# SparkFun-LSM9DS1-Breakout.net
KiCad netlist of a schematic drawn in EAGLE
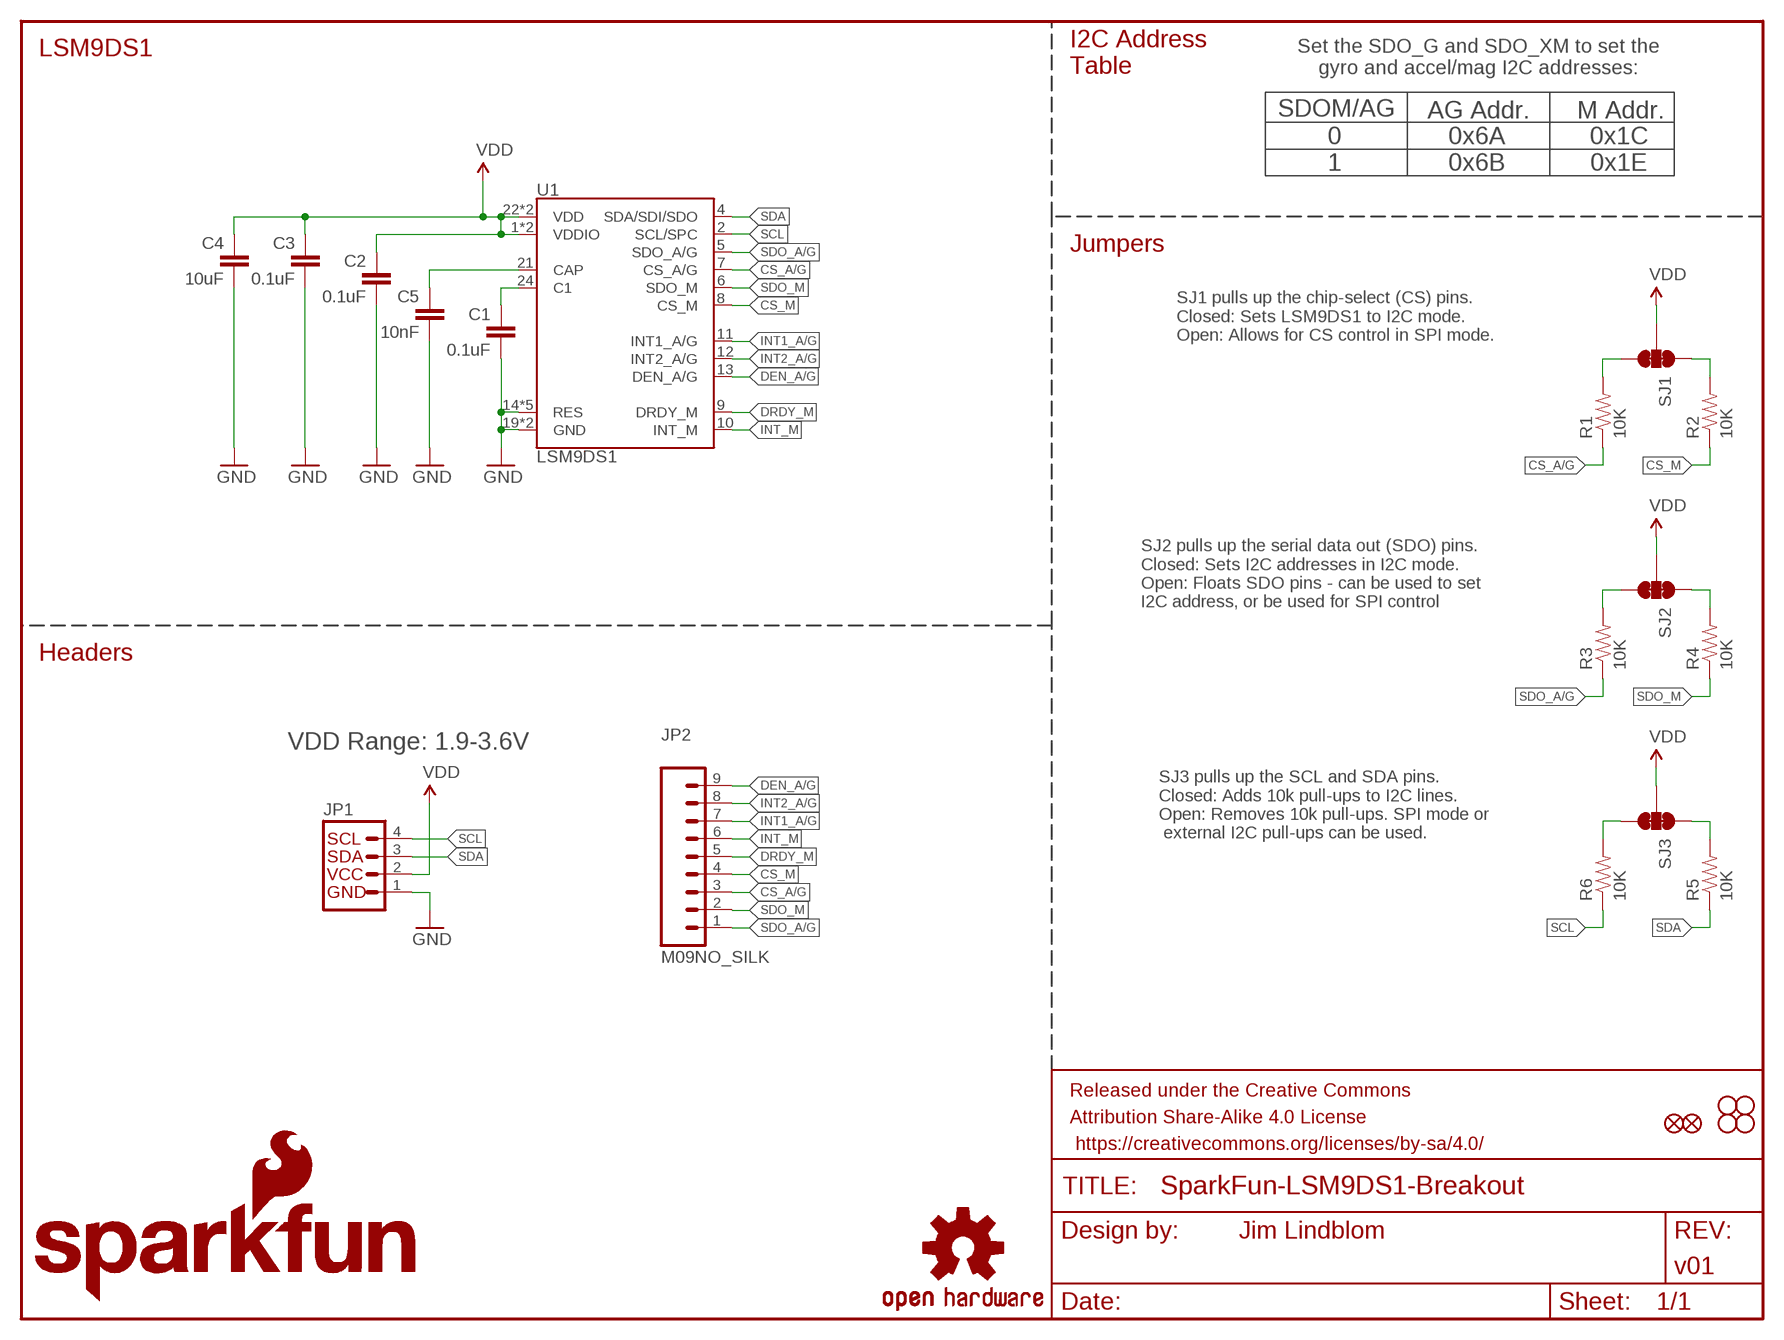
[diagram p0: schematic, sheet 1]

(export (version "E")
  (design (tool "Eeschema 10.0.6"))
  (components
    (comp (ref "C1")
      (value "0.1uF")
      (footprint "eagle-import:0603-CAP")
      (libsource (lib "eagle-import") (part "0.1UF-25V(+80/-20%)(0603)"))
    )
    (comp (ref "C2")
      (value "0.1uF")
      (footprint "eagle-import:0603-CAP")
      (libsource (lib "eagle-import") (part "0.1UF-25V(+80/-20%)(0603)"))
    )
    (comp (ref "C3")
      (value "0.1uF")
      (footprint "eagle-import:0603-CAP")
      (libsource (lib "eagle-import") (part "0.1UF-25V(+80/-20%)(0603)"))
    )
    (comp (ref "C4")
      (value "10uF")
      (footprint "eagle-import:0603-CAP")
      (libsource (lib "eagle-import") (part "10UF-6.3V-20%(0603)"))
    )
    (comp (ref "C5")
      (value "10nF")
      (footprint "eagle-import:0603-CAP")
      (libsource (lib "eagle-import") (part "10NF/10000PF-50V-10%(0603)"))
    )
    (comp (ref "FID1")
      (value "FIDUCIAL1X2")
      (footprint "eagle-import:FIDUCIAL-1X2")
      (libsource (lib "eagle-import") (part "FIDUCIAL1X2"))
    )
    (comp (ref "FID2")
      (value "FIDUCIAL1X2")
      (footprint "eagle-import:FIDUCIAL-1X2")
      (libsource (lib "eagle-import") (part "FIDUCIAL1X2"))
    )
    (comp (ref "FRAME1")
      (value "FRAME-LETTER")
      (footprint "eagle-import:CREATIVE_COMMONS")
      (fields (field (name "DESIGNER") "Jim Lindblom"))
      (libsource (lib "eagle-import") (part "FRAME-LETTER"))
    )
    (comp (ref "JP1")
      (value "I2C_STANDARD_NO_SILK")
      (footprint "eagle-import:1X04_NO_SILK")
      (libsource (lib "eagle-import") (part "I2C_STANDARD_NO_SILK"))
    )
    (comp (ref "JP2")
      (value "M09NO_SILK")
      (footprint "eagle-import:1X09_NO_SILK")
      (libsource (lib "eagle-import") (part "M09NO_SILK"))
    )
    (comp (ref "LOGO1")
      (value "SFE_LOGO_NAME.1_INCH")
      (footprint "eagle-import:SFE_LOGO_NAME_.1")
      (libsource (lib "eagle-import") (part "SFE_LOGO_NAME.1_INCH"))
    )
    (comp (ref "LOGO2")
      (value "SFE_LOGO_FLAME.2_INCH")
      (footprint "eagle-import:SFE_LOGO_FLAME_.2")
      (libsource (lib "eagle-import") (part "SFE_LOGO_FLAME.2_INCH"))
    )
    (comp (ref "LOGO3")
      (value "OSHW-LOGOS")
      (footprint "eagle-import:OSHW-LOGO-S")
      (libsource (lib "eagle-import") (part "OSHW-LOGOS"))
    )
    (comp (ref "R1")
      (value "10K")
      (footprint "eagle-import:0603-RES")
      (libsource (lib "eagle-import") (part "10KOHM-1/10W-1%(0603)0603"))
    )
    (comp (ref "R2")
      (value "10K")
      (footprint "eagle-import:0603-RES")
      (libsource (lib "eagle-import") (part "10KOHM-1/10W-1%(0603)0603"))
    )
    (comp (ref "R3")
      (value "10K")
      (footprint "eagle-import:0603-RES")
      (libsource (lib "eagle-import") (part "10KOHM-1/10W-1%(0603)0603"))
    )
    (comp (ref "R4")
      (value "10K")
      (footprint "eagle-import:0603-RES")
      (libsource (lib "eagle-import") (part "10KOHM-1/10W-1%(0603)0603"))
    )
    (comp (ref "R5")
      (value "10K")
      (footprint "eagle-import:0603-RES")
      (libsource (lib "eagle-import") (part "10KOHM-1/10W-1%(0603)0603"))
    )
    (comp (ref "R6")
      (value "10K")
      (footprint "eagle-import:0603-RES")
      (libsource (lib "eagle-import") (part "10KOHM-1/10W-1%(0603)0603"))
    )
    (comp (ref "SJ1")
      (value "JUMPER-PAD-3-NC_BY_TRACE")
      (footprint "eagle-import:PAD-JUMPER-3-3OF3_NC_BY_TRACE_YES_SILK_FULL_BOX")
      (libsource (lib "eagle-import") (part "JUMPER-PAD-3-NC_BY_TRACE"))
    )
    (comp (ref "SJ2")
      (value "JUMPER-PAD-3-NC_BY_TRACE")
      (footprint "eagle-import:PAD-JUMPER-3-3OF3_NC_BY_TRACE_YES_SILK_FULL_BOX")
      (libsource (lib "eagle-import") (part "JUMPER-PAD-3-NC_BY_TRACE"))
    )
    (comp (ref "SJ3")
      (value "JUMPER-PAD-3-NC_BY_TRACE")
      (footprint "eagle-import:PAD-JUMPER-3-3OF3_NC_BY_TRACE_YES_SILK_FULL_BOX")
      (libsource (lib "eagle-import") (part "JUMPER-PAD-3-NC_BY_TRACE"))
    )
    (comp (ref "STANDOFF1")
      (value "STAND-OFF")
      (footprint "eagle-import:STAND-OFF")
      (libsource (lib "eagle-import") (part "STAND-OFF"))
    )
    (comp (ref "STANDOFF2")
      (value "STAND-OFF")
      (footprint "eagle-import:STAND-OFF")
      (libsource (lib "eagle-import") (part "STAND-OFF"))
    )
    (comp (ref "STANDOFF3")
      (value "STAND-OFF")
      (footprint "eagle-import:STAND-OFF")
      (libsource (lib "eagle-import") (part "STAND-OFF"))
    )
    (comp (ref "STANDOFF4")
      (value "STAND-OFF")
      (footprint "eagle-import:STAND-OFF")
      (libsource (lib "eagle-import") (part "STAND-OFF"))
    )
    (comp (ref "U1")
      (value "LSM9DS1")
      (footprint "eagle-import:LGA24-8X4")
      (libsource (lib "eagle-import") (part "LSM9DS1"))
    )
  )
  (nets
    (net (code "1") (name "CS_A{slash}G") (class "Default")
      (node (ref "JP2") (pin "3") (pinfunction "3_3") (pintype "passive"))
      (node (ref "R1") (pin "1") (pinfunction "1_1") (pintype "passive"))
      (node (ref "U1") (pin "7") (pinfunction "CS_A/G_7") (pintype "bidirectional"))
    )
    (net (code "2") (name "CS_M") (class "Default")
      (node (ref "JP2") (pin "4") (pinfunction "4_4") (pintype "passive"))
      (node (ref "R2") (pin "1") (pinfunction "1_1") (pintype "passive"))
      (node (ref "U1") (pin "8") (pinfunction "CS_M_8") (pintype "bidirectional"))
    )
    (net (code "3") (name "DEN_A{slash}G") (class "Default")
      (node (ref "JP2") (pin "9") (pinfunction "9_9") (pintype "passive"))
      (node (ref "U1") (pin "13") (pinfunction "DEN_A/G_13") (pintype "bidirectional"))
    )
    (net (code "4") (name "DRDY_M") (class "Default")
      (node (ref "JP2") (pin "5") (pinfunction "5_5") (pintype "passive"))
      (node (ref "U1") (pin "9") (pinfunction "DRDY_M_9") (pintype "bidirectional"))
    )
    (net (code "5") (name "GND") (class "Default")
      (node (ref "C1") (pin "2") (pinfunction "2_2") (pintype "passive"))
      (node (ref "C2") (pin "2") (pinfunction "2_2") (pintype "passive"))
      (node (ref "C3") (pin "2") (pinfunction "2_2") (pintype "passive"))
      (node (ref "C4") (pin "2") (pinfunction "2_2") (pintype "passive"))
      (node (ref "C5") (pin "2") (pinfunction "2_2") (pintype "passive"))
      (node (ref "JP1") (pin "1") (pinfunction "1_1") (pintype "passive"))
      (node (ref "U1") (pin "14") (pinfunction "RES_14") (pintype "bidirectional"))
      (node (ref "U1") (pin "15") (pinfunction "RES_15") (pintype "bidirectional"))
      (node (ref "U1") (pin "16") (pinfunction "RES_16") (pintype "bidirectional"))
      (node (ref "U1") (pin "17") (pinfunction "RES_17") (pintype "bidirectional"))
      (node (ref "U1") (pin "18") (pinfunction "RES_18") (pintype "bidirectional"))
      (node (ref "U1") (pin "19") (pinfunction "GND_19") (pintype "bidirectional"))
      (node (ref "U1") (pin "20") (pinfunction "GND_20") (pintype "bidirectional"))
    )
    (net (code "6") (name "INT1_A{slash}G") (class "Default")
      (node (ref "JP2") (pin "7") (pinfunction "7_7") (pintype "passive"))
      (node (ref "U1") (pin "11") (pinfunction "INT1_A/G_11") (pintype "bidirectional"))
    )
    (net (code "7") (name "INT2_A{slash}G") (class "Default")
      (node (ref "JP2") (pin "8") (pinfunction "8_8") (pintype "passive"))
      (node (ref "U1") (pin "12") (pinfunction "INT2_A/G_12") (pintype "bidirectional"))
    )
    (net (code "8") (name "INT_M") (class "Default")
      (node (ref "JP2") (pin "6") (pinfunction "6_6") (pintype "passive"))
      (node (ref "U1") (pin "10") (pinfunction "INT_M_10") (pintype "bidirectional"))
    )
    (net (code "9") (name "Net-(R1-Pad2)") (class "Default")
      (node (ref "R1") (pin "2") (pinfunction "2_2") (pintype "passive"))
      (node (ref "SJ1") (pin "3") (pinfunction "3_3") (pintype "passive"))
    )
    (net (code "10") (name "Net-(R2-Pad2)") (class "Default")
      (node (ref "R2") (pin "2") (pinfunction "2_2") (pintype "passive"))
      (node (ref "SJ1") (pin "1") (pinfunction "1_1") (pintype "passive"))
    )
    (net (code "11") (name "Net-(R3-Pad2)") (class "Default")
      (node (ref "R3") (pin "2") (pinfunction "2_2") (pintype "passive"))
      (node (ref "SJ2") (pin "3") (pinfunction "3_3") (pintype "passive"))
    )
    (net (code "12") (name "Net-(R4-Pad2)") (class "Default")
      (node (ref "R4") (pin "2") (pinfunction "2_2") (pintype "passive"))
      (node (ref "SJ2") (pin "1") (pinfunction "1_1") (pintype "passive"))
    )
    (net (code "13") (name "Net-(R5-Pad2)") (class "Default")
      (node (ref "R5") (pin "2") (pinfunction "2_2") (pintype "passive"))
      (node (ref "SJ3") (pin "1") (pinfunction "1_1") (pintype "passive"))
    )
    (net (code "14") (name "Net-(R6-Pad2)") (class "Default")
      (node (ref "R6") (pin "2") (pinfunction "2_2") (pintype "passive"))
      (node (ref "SJ3") (pin "3") (pinfunction "3_3") (pintype "passive"))
    )
    (net (code "15") (name "Net-(U1-C1)") (class "Default")
      (node (ref "C1") (pin "1") (pinfunction "1_1") (pintype "passive"))
      (node (ref "U1") (pin "24") (pinfunction "C1_24") (pintype "bidirectional"))
    )
    (net (code "16") (name "Net-(U1-CAP)") (class "Default")
      (node (ref "C5") (pin "1") (pinfunction "1_1") (pintype "passive"))
      (node (ref "U1") (pin "21") (pinfunction "CAP_21") (pintype "bidirectional"))
    )
    (net (code "17") (name "SCL") (class "Default")
      (node (ref "JP1") (pin "4") (pinfunction "4_4") (pintype "passive"))
      (node (ref "R6") (pin "1") (pinfunction "1_1") (pintype "passive"))
      (node (ref "U1") (pin "2") (pinfunction "SCL/SPC_2") (pintype "bidirectional"))
    )
    (net (code "18") (name "SDA") (class "Default")
      (node (ref "JP1") (pin "3") (pinfunction "3_3") (pintype "passive"))
      (node (ref "R5") (pin "1") (pinfunction "1_1") (pintype "passive"))
      (node (ref "U1") (pin "4") (pinfunction "SDA/SDI/SDO_4") (pintype "bidirectional"))
    )
    (net (code "19") (name "SDO_A{slash}G") (class "Default")
      (node (ref "JP2") (pin "1") (pinfunction "1_1") (pintype "passive"))
      (node (ref "R3") (pin "1") (pinfunction "1_1") (pintype "passive"))
      (node (ref "U1") (pin "5") (pinfunction "SDO_A/G_5") (pintype "bidirectional"))
    )
    (net (code "20") (name "SDO_M") (class "Default")
      (node (ref "JP2") (pin "2") (pinfunction "2_2") (pintype "passive"))
      (node (ref "R4") (pin "1") (pinfunction "1_1") (pintype "passive"))
      (node (ref "U1") (pin "6") (pinfunction "SDO_M_6") (pintype "bidirectional"))
    )
    (net (code "21") (name "VDD") (class "Default")
      (node (ref "C2") (pin "1") (pinfunction "1_1") (pintype "passive"))
      (node (ref "C3") (pin "1") (pinfunction "1_1") (pintype "passive"))
      (node (ref "C4") (pin "1") (pinfunction "1_1") (pintype "passive"))
      (node (ref "JP1") (pin "2") (pinfunction "2_2") (pintype "passive"))
      (node (ref "SJ1") (pin "2") (pinfunction "2_2") (pintype "passive"))
      (node (ref "SJ2") (pin "2") (pinfunction "2_2") (pintype "passive"))
      (node (ref "SJ3") (pin "2") (pinfunction "2_2") (pintype "passive"))
      (node (ref "U1") (pin "1") (pinfunction "VDDIO_1") (pintype "bidirectional"))
      (node (ref "U1") (pin "22") (pinfunction "VDD_22") (pintype "bidirectional"))
      (node (ref "U1") (pin "23") (pinfunction "VDD_23") (pintype "bidirectional"))
      (node (ref "U1") (pin "3") (pinfunction "VDDIO_3") (pintype "bidirectional"))
    )
  )
)
